# PSU_board.net
KiCad netlist of a schematic drawn in EAGLE
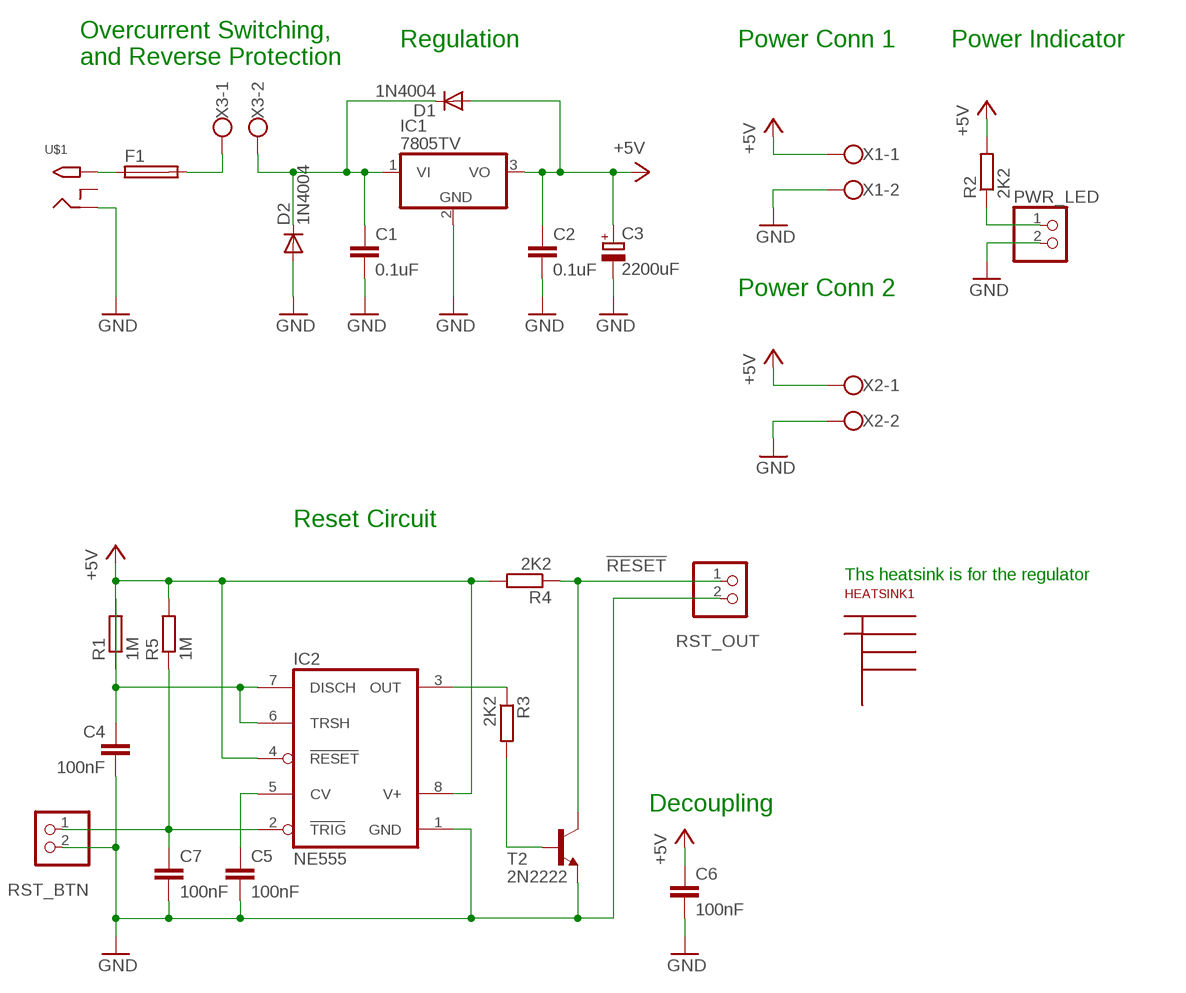
[diagram p0: schematic, sheet 1]

(export (version "E")
  (design (tool "Eeschema 10.0.6"))
  (components
    (comp (ref "C1")
      (value "0.1uF")
      (footprint "eagle-import:C025-025X050")
      (libsource (lib "eagle-import") (part "C-EU025-025X050"))
    )
    (comp (ref "C2")
      (value "0.1uF")
      (footprint "eagle-import:C025-025X050")
      (libsource (lib "eagle-import") (part "C-EU025-025X050"))
    )
    (comp (ref "C3")
      (value "2200uF")
      (footprint "eagle-import:E7,5-18")
      (libsource (lib "eagle-import") (part "CPOL-EUE7.5-18"))
    )
    (comp (ref "C4")
      (value "100nF")
      (footprint "eagle-import:C025-025X050")
      (libsource (lib "eagle-import") (part "C-EU025-025X050"))
    )
    (comp (ref "C5")
      (value "100nF")
      (footprint "eagle-import:C025-025X050")
      (libsource (lib "eagle-import") (part "C-EU025-025X050"))
    )
    (comp (ref "C6")
      (value "100nF")
      (footprint "eagle-import:C025-025X050")
      (libsource (lib "eagle-import") (part "C-EU025-025X050"))
    )
    (comp (ref "C7")
      (value "100nF")
      (footprint "eagle-import:C025-025X050")
      (libsource (lib "eagle-import") (part "C-EU025-025X050"))
    )
    (comp (ref "D1")
      (value "1N4004")
      (footprint "eagle-import:DO41-10")
      (libsource (lib "eagle-import") (part "1N4004"))
    )
    (comp (ref "D2")
      (value "1N4004")
      (footprint "eagle-import:DO41-10")
      (libsource (lib "eagle-import") (part "1N4004"))
    )
    (comp (ref "F1")
      (value "SH22,5A")
      (footprint "eagle-import:SH22,5A")
      (fields (field (name "MPN") "0031.7701.11"))
      (libsource (lib "eagle-import") (part "SH22,5A"))
    )
    (comp (ref "HEATSINK1")
      (value "FISCHER-50_HSINK")
      (footprint "eagle-import:FISHER-50")
      (libsource (lib "eagle-import") (part "FISCHER-50_HSINK"))
    )
    (comp (ref "IC1")
      (value "7805TV")
      (footprint "eagle-import:TO220V")
      (libsource (lib "eagle-import") (part "78TV05"))
    )
    (comp (ref "IC2")
      (value "NE555")
      (footprint "eagle-import:DIL08")
      (libsource (lib "eagle-import") (part "ICM7555"))
    )
    (comp (ref "PWR_LED")
      (value "PINHD-1X2")
      (footprint "eagle-import:1X02")
      (libsource (lib "eagle-import") (part "PINHD-1X2"))
    )
    (comp (ref "R1")
      (value "1M")
      (footprint "eagle-import:0207_2V")
      (libsource (lib "eagle-import") (part "R-EU_0207/2V"))
    )
    (comp (ref "R2")
      (value "2K2")
      (footprint "eagle-import:0207_10")
      (libsource (lib "eagle-import") (part "R-EU_0207/10"))
    )
    (comp (ref "R3")
      (value "2K2")
      (footprint "eagle-import:0207_2V")
      (libsource (lib "eagle-import") (part "R-EU_0207/2V"))
    )
    (comp (ref "R4")
      (value "2K2")
      (footprint "eagle-import:0207_2V")
      (libsource (lib "eagle-import") (part "R-EU_0207/2V"))
    )
    (comp (ref "R5")
      (value "1M")
      (footprint "eagle-import:0207_10")
      (libsource (lib "eagle-import") (part "R-EU_0207/10"))
    )
    (comp (ref "RST_BTN")
      (value "PINHD-1X2")
      (footprint "eagle-import:1X02")
      (libsource (lib "eagle-import") (part "PINHD-1X2"))
    )
    (comp (ref "RST_OUT")
      (value "PINHD-1X2")
      (footprint "eagle-import:1X02")
      (libsource (lib "eagle-import") (part "PINHD-1X2"))
    )
    (comp (ref "T2")
      (value "2N2222")
      (footprint "eagle-import:TO18")
      (libsource (lib "eagle-import") (part "2N2222"))
    )
    (comp (ref "U$1")
      (value "2.1MMJACKTHM")
      (footprint "eagle-import:PJ-102A")
      (libsource (lib "eagle-import") (part "2.1MMJACKTHM"))
    )
    (comp (ref "X1")
      (value "W237-102")
      (footprint "eagle-import:W237-102")
      (fields (field (name "MPN") "237-102"))
      (libsource (lib "eagle-import") (part "W237-102"))
    )
    (comp (ref "X2")
      (value "W237-102")
      (footprint "eagle-import:W237-102")
      (fields (field (name "MPN") "237-102"))
      (libsource (lib "eagle-import") (part "W237-102"))
    )
    (comp (ref "X3")
      (value "W237-102")
      (footprint "eagle-import:W237-102")
      (fields (field (name "MPN") "237-102"))
      (libsource (lib "eagle-import") (part "W237-102"))
    )
  )
  (nets
    (net (code "1") (name "+5V") (class "Default")
      (node (ref "C2") (pin "1") (pinfunction "1_1") (pintype "passive"))
      (node (ref "C3") (pin "+") (pinfunction "+_+") (pintype "passive"))
      (node (ref "C6") (pin "1") (pinfunction "1_1") (pintype "passive"))
      (node (ref "D1") (pin "A") (pinfunction "A_A") (pintype "passive"))
      (node (ref "IC1") (pin "3") (pinfunction "VO_3") (pintype "passive"))
      (node (ref "IC2") (pin "4") (pinfunction "RESET_4") (pintype "input"))
      (node (ref "IC2") (pin "8") (pinfunction "V+_8") (pintype "power_in"))
      (node (ref "R1") (pin "1") (pinfunction "1_1") (pintype "passive"))
      (node (ref "R2") (pin "2") (pinfunction "2_2") (pintype "passive"))
      (node (ref "R4") (pin "2") (pinfunction "2_2") (pintype "passive"))
      (node (ref "R5") (pin "2") (pinfunction "2_2") (pintype "passive"))
      (node (ref "X1") (pin "1") (pinfunction "KL_1") (pintype "passive"))
      (node (ref "X2") (pin "1") (pinfunction "KL_1") (pintype "passive"))
    )
    (net (code "2") (name "/~{RESET}") (class "Default")
      (node (ref "R4") (pin "1") (pinfunction "1_1") (pintype "passive"))
      (node (ref "RST_OUT") (pin "1") (pinfunction "1_1") (pintype "passive"))
      (node (ref "T2") (pin "3") (pinfunction "C_3") (pintype "passive"))
    )
    (net (code "3") (name "GND") (class "Default")
      (node (ref "C1") (pin "2") (pinfunction "2_2") (pintype "passive"))
      (node (ref "C2") (pin "2") (pinfunction "2_2") (pintype "passive"))
      (node (ref "C3") (pin "-") (pinfunction "-_-") (pintype "passive"))
      (node (ref "C4") (pin "2") (pinfunction "2_2") (pintype "passive"))
      (node (ref "C5") (pin "2") (pinfunction "2_2") (pintype "passive"))
      (node (ref "C6") (pin "2") (pinfunction "2_2") (pintype "passive"))
      (node (ref "C7") (pin "2") (pinfunction "2_2") (pintype "passive"))
      (node (ref "D2") (pin "A") (pinfunction "A_A") (pintype "passive"))
      (node (ref "IC1") (pin "2") (pinfunction "GND_2") (pintype "passive"))
      (node (ref "IC2") (pin "1") (pinfunction "GND_1") (pintype "power_in"))
      (node (ref "PWR_LED") (pin "2") (pinfunction "2_2") (pintype "passive"))
      (node (ref "RST_BTN") (pin "2") (pinfunction "2_2") (pintype "passive"))
      (node (ref "RST_OUT") (pin "2") (pinfunction "2_2") (pintype "passive"))
      (node (ref "T2") (pin "1") (pinfunction "E_1") (pintype "passive"))
      (node (ref "U$1") (pin "RING") (pinfunction "RING_RING") (pintype "bidirectional"))
      (node (ref "X1") (pin "2") (pinfunction "KL_2") (pintype "passive"))
      (node (ref "X2") (pin "2") (pinfunction "KL_2") (pintype "passive"))
    )
    (net (code "4") (name "Net-(F1-Pad1)") (class "Default")
      (node (ref "F1") (pin "1") (pinfunction "1_1") (pintype "passive"))
      (node (ref "U$1") (pin "TIP") (pinfunction "TIP_TIP") (pintype "bidirectional"))
    )
    (net (code "5") (name "Net-(IC1-VI)") (class "Default")
      (node (ref "C1") (pin "1") (pinfunction "1_1") (pintype "passive"))
      (node (ref "D1") (pin "C") (pinfunction "C_C") (pintype "passive"))
      (node (ref "D2") (pin "C") (pinfunction "C_C") (pintype "passive"))
      (node (ref "IC1") (pin "1") (pinfunction "VI_1") (pintype "input"))
      (node (ref "X3") (pin "2") (pinfunction "KL_2") (pintype "passive"))
    )
    (net (code "6") (name "Net-(IC2-CV)") (class "Default")
      (node (ref "C5") (pin "1") (pinfunction "1_1") (pintype "passive"))
      (node (ref "IC2") (pin "5") (pinfunction "CV_5") (pintype "passive"))
    )
    (net (code "7") (name "Net-(IC2-DISCH)") (class "Default")
      (node (ref "C4") (pin "1") (pinfunction "1_1") (pintype "passive"))
      (node (ref "IC2") (pin "6") (pinfunction "TRSH_6") (pintype "input"))
      (node (ref "IC2") (pin "7") (pinfunction "DISCH_7") (pintype "input"))
      (node (ref "R1") (pin "2") (pinfunction "2_2") (pintype "passive"))
    )
    (net (code "8") (name "Net-(IC2-OUT)") (class "Default")
      (node (ref "IC2") (pin "3") (pinfunction "OUT_3") (pintype "output"))
      (node (ref "R3") (pin "1") (pinfunction "1_1") (pintype "passive"))
    )
    (net (code "9") (name "Net-(IC2-TRIG)") (class "Default")
      (node (ref "C7") (pin "1") (pinfunction "1_1") (pintype "passive"))
      (node (ref "IC2") (pin "2") (pinfunction "TRIG_2") (pintype "bidirectional"))
      (node (ref "R5") (pin "1") (pinfunction "1_1") (pintype "passive"))
      (node (ref "RST_BTN") (pin "1") (pinfunction "1_1") (pintype "passive"))
    )
    (net (code "10") (name "Net-(PWR_LED-Pad1)") (class "Default")
      (node (ref "PWR_LED") (pin "1") (pinfunction "1_1") (pintype "passive"))
      (node (ref "R2") (pin "1") (pinfunction "1_1") (pintype "passive"))
    )
    (net (code "11") (name "Net-(T2-B)") (class "Default")
      (node (ref "R3") (pin "2") (pinfunction "2_2") (pintype "passive"))
      (node (ref "T2") (pin "2") (pinfunction "B_2") (pintype "passive"))
    )
    (net (code "12") (name "Net-(X3A-KL)") (class "Default")
      (node (ref "F1") (pin "2") (pinfunction "2_2") (pintype "passive"))
      (node (ref "X3") (pin "1") (pinfunction "KL_1") (pintype "passive"))
    )
    (net (code "13") (name "unconnected-(U$1-PadRING_SW)") (class "Default")
      (node (ref "U$1") (pin "RING_SW") (pinfunction "RING_SW_RING_SW") (pintype "bidirectional"))
    )
  )
)
